# espdh11new.net
KiCad netlist of a schematic drawn in EAGLE
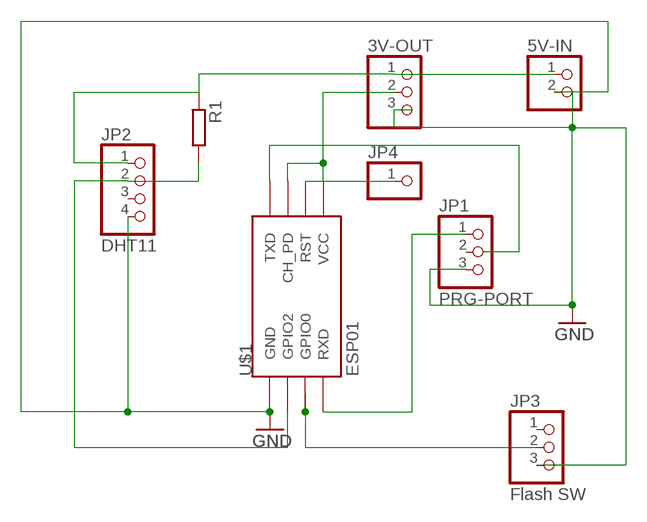
[diagram p0: schematic, sheet 1]

(export (version "E")
  (design (tool "Eeschema 10.0.6"))
  (components
    (comp (ref "3V-OUT")
      (value "PINHD-1X3")
      (footprint "eagle-import:1X03")
      (libsource (lib "eagle-import") (part "PINHD-1X3"))
    )
    (comp (ref "5V-IN")
      (value "PINHD-1X2")
      (footprint "eagle-import:1X02")
      (libsource (lib "eagle-import") (part "PINHD-1X2"))
    )
    (comp (ref "JP1")
      (value "PRG-PORT")
      (footprint "eagle-import:1X03")
      (libsource (lib "eagle-import") (part "PINHD-1X3"))
    )
    (comp (ref "JP2")
      (value "DHT11")
      (footprint "eagle-import:1X04")
      (libsource (lib "eagle-import") (part "PINHD-1X4"))
    )
    (comp (ref "JP3")
      (value "Flash SW")
      (footprint "eagle-import:1X03_90")
      (libsource (lib "eagle-import") (part "PINHD-1X3/90"))
    )
    (comp (ref "JP4")
      (value "PINHD-1X1")
      (footprint "eagle-import:1X01")
      (libsource (lib "eagle-import") (part "PINHD-1X1"))
    )
    (comp (ref "R1")
      (value "R-EU_0204/5")
      (footprint "eagle-import:0204_5")
      (libsource (lib "eagle-import") (part "R-EU_0204/5"))
    )
    (comp (ref "U$1")
      (value "ESP01")
      (footprint "eagle-import:ESP01")
      (libsource (lib "eagle-import") (part "ESP01"))
    )
  )
  (nets
    (net (code "1") (name "GND") (class "Default")
      (node (ref "3V-OUT") (pin "3") (pinfunction "3_3") (pintype "passive"))
      (node (ref "5V-IN") (pin "2") (pinfunction "2_2") (pintype "passive"))
      (node (ref "JP1") (pin "3") (pinfunction "3_3") (pintype "passive"))
      (node (ref "JP2") (pin "4") (pinfunction "4_4") (pintype "passive"))
      (node (ref "JP3") (pin "3") (pinfunction "3_3") (pintype "passive"))
      (node (ref "U$1") (pin "GND") (pinfunction "GND_GND") (pintype "bidirectional"))
    )
    (net (code "2") (name "Net-(3V-OUT-Pad1)") (class "Default")
      (node (ref "3V-OUT") (pin "1") (pinfunction "1_1") (pintype "passive"))
      (node (ref "5V-IN") (pin "1") (pinfunction "1_1") (pintype "passive"))
      (node (ref "JP2") (pin "1") (pinfunction "1_1") (pintype "passive"))
      (node (ref "R1") (pin "1") (pinfunction "1_1") (pintype "passive"))
    )
    (net (code "3") (name "Net-(3V-OUT-Pad2)") (class "Default")
      (node (ref "3V-OUT") (pin "2") (pinfunction "2_2") (pintype "passive"))
      (node (ref "U$1") (pin "CH_PD") (pinfunction "CH_PD_CH_PD") (pintype "bidirectional"))
      (node (ref "U$1") (pin "VCC") (pinfunction "VCC_VCC") (pintype "bidirectional"))
    )
    (net (code "4") (name "Net-(JP2-Pad2)") (class "Default")
      (node (ref "JP2") (pin "2") (pinfunction "2_2") (pintype "passive"))
      (node (ref "R1") (pin "2") (pinfunction "2_2") (pintype "passive"))
      (node (ref "U$1") (pin "GPIO2") (pinfunction "GPIO2_GPIO2") (pintype "bidirectional"))
    )
    (net (code "5") (name "Net-(JP3-Pad2)") (class "Default")
      (node (ref "JP3") (pin "2") (pinfunction "2_2") (pintype "passive"))
      (node (ref "U$1") (pin "GPIO0") (pinfunction "GPIO0_GPIO0") (pintype "bidirectional"))
    )
    (net (code "6") (name "Net-(JP4-Pad1)") (class "Default")
      (node (ref "JP4") (pin "1") (pinfunction "1_1") (pintype "passive"))
      (node (ref "U$1") (pin "RST") (pinfunction "RST_RST") (pintype "bidirectional"))
    )
    (net (code "7") (name "Net-(U$1-RXD)") (class "Default")
      (node (ref "JP1") (pin "1") (pinfunction "1_1") (pintype "passive"))
      (node (ref "U$1") (pin "RX") (pinfunction "RXD_RX") (pintype "bidirectional"))
    )
    (net (code "8") (name "unconnected-(JP1-Pad2)") (class "Default")
      (node (ref "JP1") (pin "2") (pinfunction "2_2") (pintype "passive"))
    )
    (net (code "9") (name "unconnected-(JP2-Pad3)") (class "Default")
      (node (ref "JP2") (pin "3") (pinfunction "3_3") (pintype "passive"))
    )
    (net (code "10") (name "unconnected-(JP3-Pad1)") (class "Default")
      (node (ref "JP3") (pin "1") (pinfunction "1_1") (pintype "passive"))
    )
    (net (code "11") (name "unconnected-(U$1-TXD-PadTX)") (class "Default")
      (node (ref "U$1") (pin "TX") (pinfunction "TXD_TX") (pintype "bidirectional"))
    )
  )
)
